# PWM.net
KiCad netlist of a schematic drawn in Altium Designer
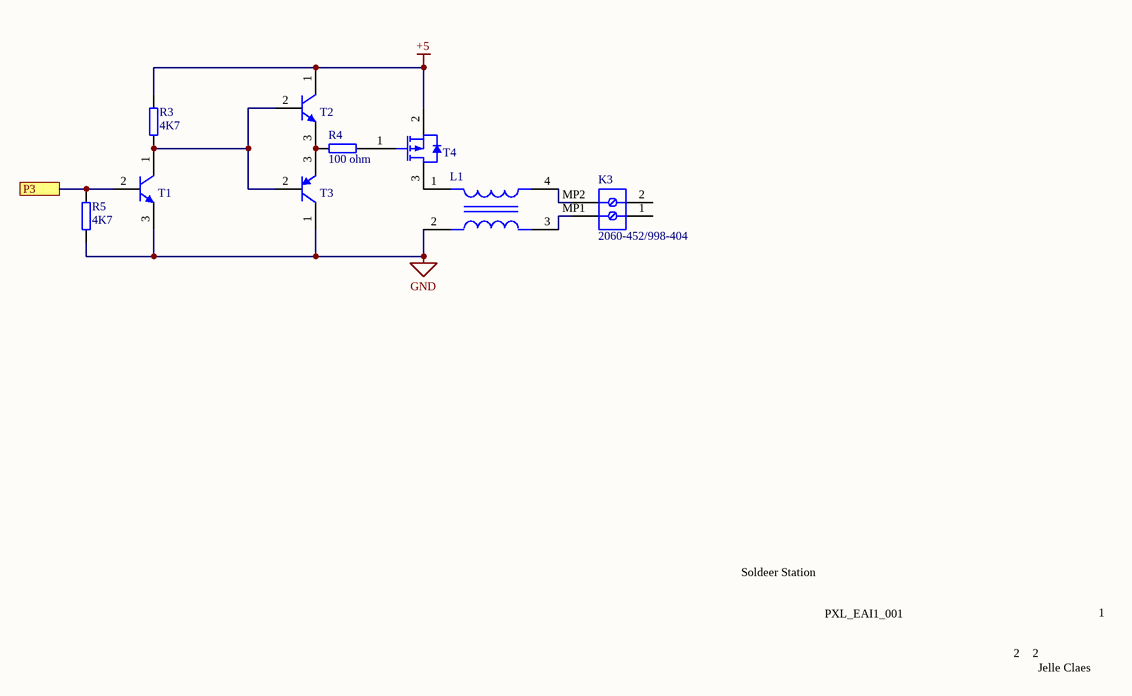
[diagram p0: PWM.SchDoc]

(export (version "E")
  (design (tool "Eeschema 10.0.6"))
  (components
    (comp (ref "K3")
      (value "2060-452/998-404")
      (footprint "WAGO-2060-452_V")
      (description "Terminal Block, Pitch 4 mm, 1 x 2 Position, Height 4.5 mm, -60 to 105 degC, RoHS, Tape and Reel")
      (fields (field (name "MANUFACTURER") "WAGO"))
      (libsource (lib "soldeerstation") (part "WAGO-2060"))
    )
    (comp (ref "L1")
      (value "Common_Mode_Choke")
      (footprint "2545")
      (libsource (lib "soldeerstation") (part "Common_Mode_Choke"))
    )
    (comp (ref "R3")
      (value "4K7")
      (footprint "R_0805_M")
      (fields (field (name "MANUFACTURER") "Vishay Dale") (field (name "PART NUMBER") "CRCW08050000Z0EA"))
      (libsource (lib "soldeerstation") (part "Resistor"))
    )
    (comp (ref "R4")
      (value "100 ohm")
      (footprint "R_0805_M")
      (fields (field (name "MANUFACTURER") "Vishay Dale") (field (name "PART NUMBER") "CRCW08050000Z0EA"))
      (libsource (lib "soldeerstation") (part "Resistor"))
    )
    (comp (ref "R5")
      (value "4K7")
      (footprint "R_0805_M")
      (fields (field (name "MANUFACTURER") "Vishay Dale") (field (name "PART NUMBER") "CRCW08050000Z0EA"))
      (libsource (lib "soldeerstation") (part "Resistor"))
    )
    (comp (ref "T1")
      (value "Transistor_NPN")
      (footprint "SOT_23")
      (fields (field (name "MANUFACTURER") "On Semiconductor") (field (name "PARTNUMBER") "BC547C"))
      (libsource (lib "soldeerstation") (part "Transistor_NPN"))
    )
    (comp (ref "T2")
      (value "Transistor_NPN")
      (footprint "SOT_23")
      (fields (field (name "MANUFACTURER") "On Semiconductor") (field (name "PARTNUMBER") "BC547C"))
      (libsource (lib "soldeerstation") (part "Transistor_NPN"))
    )
    (comp (ref "T3")
      (value "Transistor_PNP")
      (footprint "SOT_23")
      (fields (field (name "MANUFACTURER") "On Semiconductor") (field (name "PARTNUMBER") "BC557C"))
      (libsource (lib "soldeerstation") (part "Transistor_PNP"))
    )
    (comp (ref "T4")
      (value "MOSFET_P")
      (footprint "TO_252")
      (fields (field (name "MANUFACTURER") "Fairchild Semiconductor"))
      (libsource (lib "soldeerstation") (part "MOSFET_P"))
    )
  )
  (nets
    (net (code "1") (name "+5") (class "Default")
      (node (ref "R3") (pin "2") (pinfunction "2_2") (pintype "passive"))
      (node (ref "T2") (pin "1") (pinfunction "C_1") (pintype "passive"))
      (node (ref "T4") (pin "2") (pinfunction "DRAIN_2") (pintype "passive"))
    )
    (net (code "2") (name "/P3") (class "Default")
      (node (ref "R5") (pin "2") (pinfunction "2_2") (pintype "passive"))
      (node (ref "T1") (pin "2") (pinfunction "B_2") (pintype "passive"))
    )
    (net (code "3") (name "GND") (class "Default")
      (node (ref "L1") (pin "2") (pinfunction "2_2") (pintype "passive"))
      (node (ref "R5") (pin "1") (pinfunction "1_1") (pintype "passive"))
      (node (ref "T1") (pin "3") (pinfunction "E_3") (pintype "passive"))
      (node (ref "T3") (pin "1") (pinfunction "C_1") (pintype "passive"))
    )
    (net (code "4") (name "Net-(K3-PadMP1)") (class "Default")
      (node (ref "K3") (pin "MP1") (pinfunction "MP1_MP1") (pintype "passive"))
      (node (ref "L1") (pin "3") (pinfunction "3_3") (pintype "passive"))
    )
    (net (code "5") (name "Net-(K3-PadMP2)") (class "Default")
      (node (ref "K3") (pin "MP2") (pinfunction "MP2_MP2") (pintype "passive"))
      (node (ref "L1") (pin "4") (pinfunction "4_4") (pintype "passive"))
    )
    (net (code "6") (name "Net-(T1-C)") (class "Default")
      (node (ref "R3") (pin "1") (pinfunction "1_1") (pintype "passive"))
      (node (ref "T1") (pin "1") (pinfunction "C_1") (pintype "passive"))
      (node (ref "T2") (pin "2") (pinfunction "B_2") (pintype "passive"))
      (node (ref "T3") (pin "2") (pinfunction "B_2") (pintype "passive"))
    )
    (net (code "7") (name "Net-(T2-E)") (class "Default")
      (node (ref "R4") (pin "2") (pinfunction "2_2") (pintype "passive"))
      (node (ref "T2") (pin "3") (pinfunction "E_3") (pintype "passive"))
      (node (ref "T3") (pin "3") (pinfunction "E_3") (pintype "passive"))
    )
    (net (code "8") (name "Net-(T4-GATE)") (class "Default")
      (node (ref "R4") (pin "1") (pinfunction "1_1") (pintype "passive"))
      (node (ref "T4") (pin "1") (pinfunction "GATE_1") (pintype "passive"))
    )
    (net (code "9") (name "Net-(T4-SOURCE)") (class "Default")
      (node (ref "L1") (pin "1") (pinfunction "1_1") (pintype "passive"))
      (node (ref "T4") (pin "3") (pinfunction "SOURCE_3") (pintype "passive"))
    )
    (net (code "10") (name "unconnected-(K3-Pad1)") (class "Default")
      (node (ref "K3") (pin "1") (pinfunction "1_1") (pintype "passive"))
    )
    (net (code "11") (name "unconnected-(K3-Pad2)") (class "Default")
      (node (ref "K3") (pin "2") (pinfunction "2_2") (pintype "passive"))
    )
  )
)
